# Tablero_Potencia_para_PDF.net
KiCad netlist of a schematic drawn in EAGLE
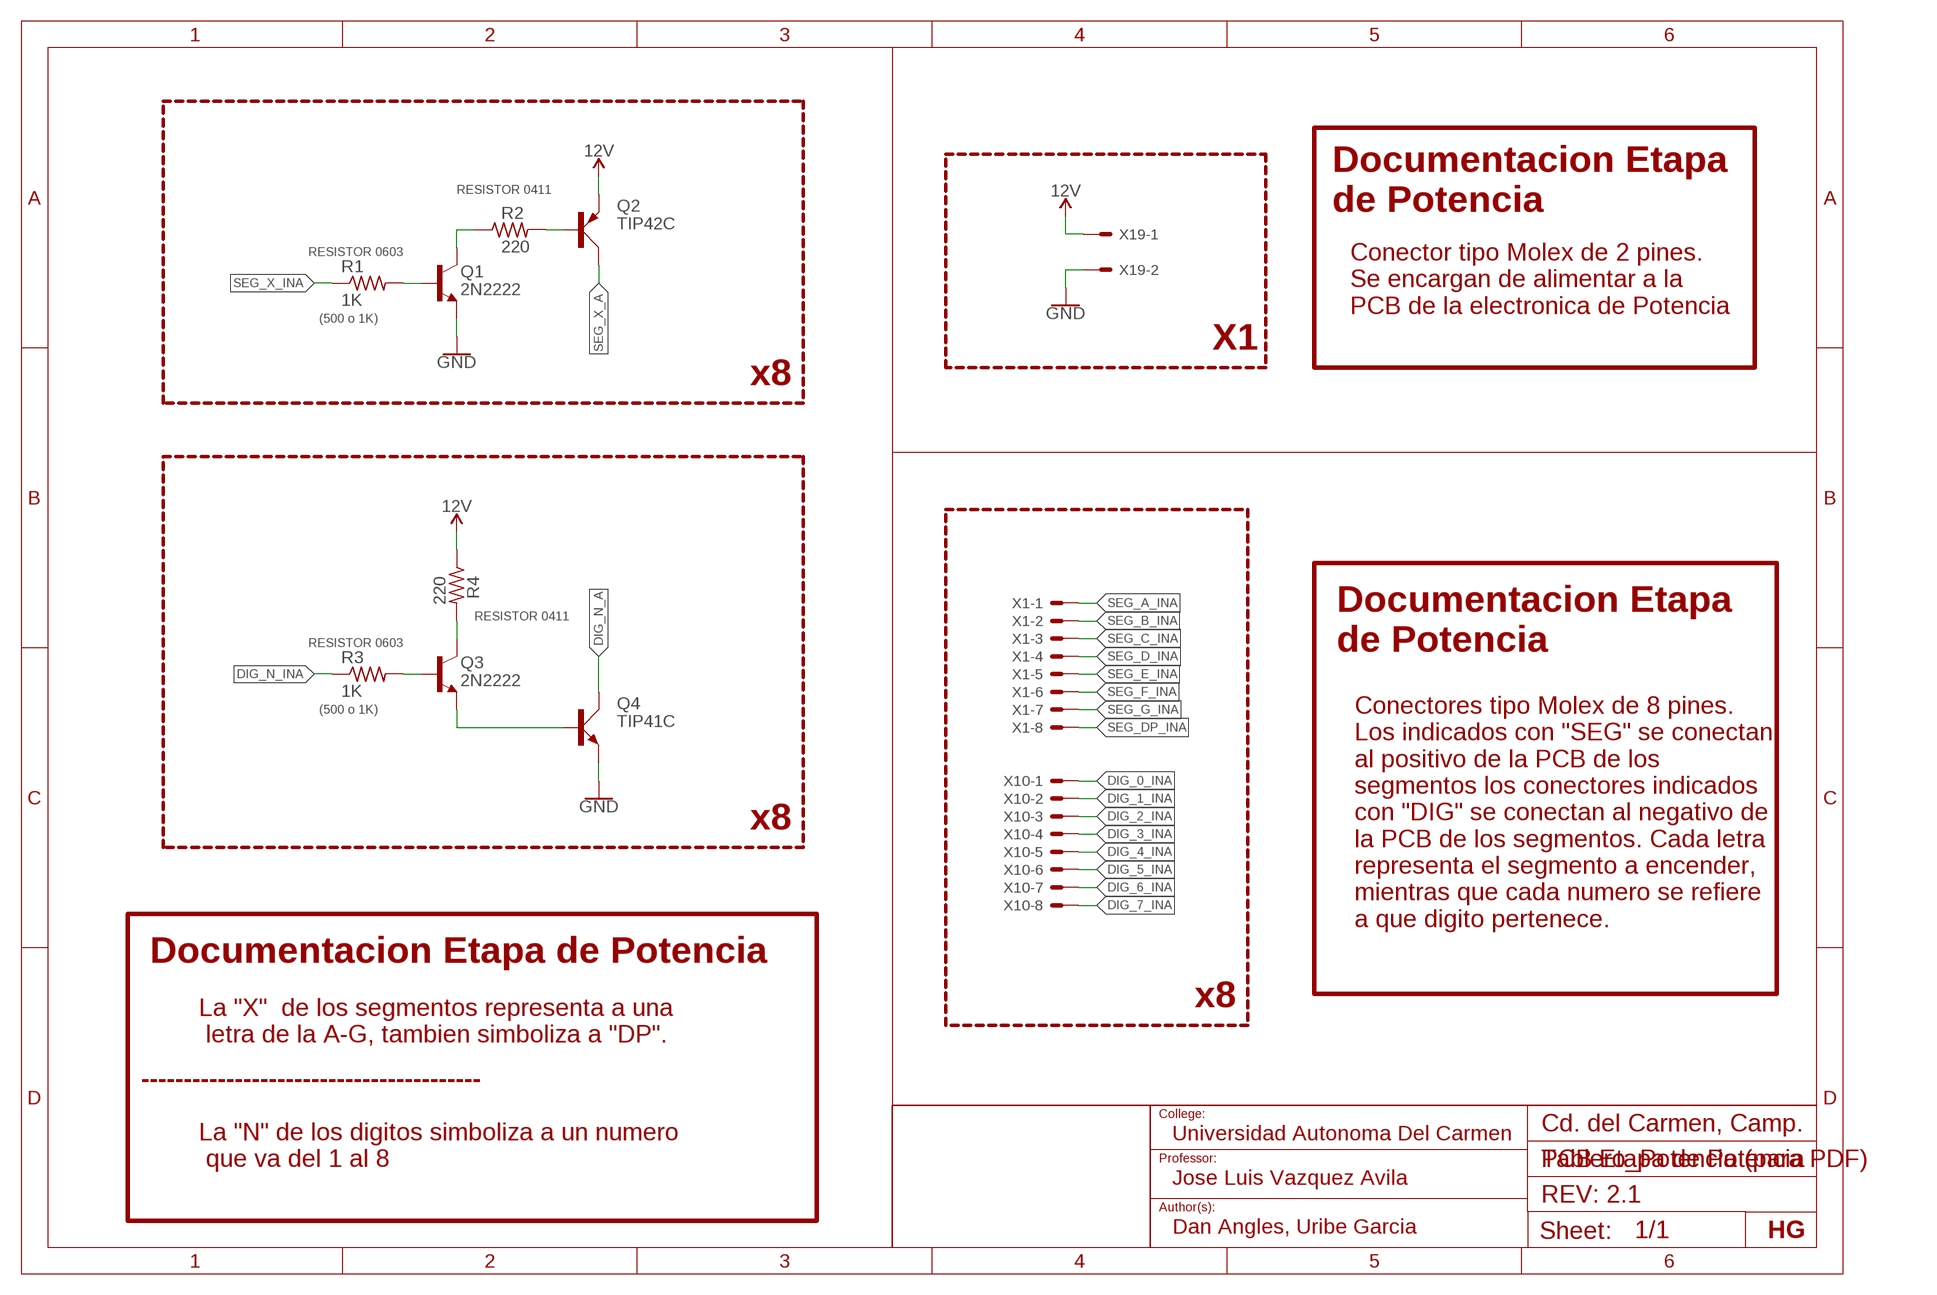
[diagram p0: schematic, sheet 1]

(export (version "E")
  (design (tool "Eeschema 10.0.6"))
  (components
    (comp (ref "Q1")
      (value "2N2222")
      (footprint "eagle-import:TO92")
      (libsource (lib "eagle-import") (part "BJT-NPNTO92"))
    )
    (comp (ref "Q2")
      (value "TIP42C")
      (footprint "eagle-import:TO220AV")
      (libsource (lib "eagle-import") (part "TIP42C"))
    )
    (comp (ref "Q3")
      (value "2N2222")
      (footprint "eagle-import:TO92")
      (libsource (lib "eagle-import") (part "BJT-NPNTO92"))
    )
    (comp (ref "Q4")
      (value "TIP41C")
      (footprint "eagle-import:TO220AV")
      (libsource (lib "eagle-import") (part "TIP41C"))
    )
    (comp (ref "R1")
      (value "1K")
      (footprint "eagle-import:R0603")
      (libsource (lib "eagle-import") (part "R-US_R0603"))
    )
    (comp (ref "R2")
      (value "220")
      (footprint "eagle-import:0411_15")
      (libsource (lib "eagle-import") (part "R-US_0411/15"))
    )
    (comp (ref "R3")
      (value "1K")
      (footprint "eagle-import:R0603")
      (libsource (lib "eagle-import") (part "R-US_R0603"))
    )
    (comp (ref "R4")
      (value "220")
      (footprint "eagle-import:0411_15")
      (libsource (lib "eagle-import") (part "R-US_0411/15"))
    )
    (comp (ref "X1")
      (value "KK-156-8")
      (footprint "eagle-import:KK-156-8")
      (fields (field (name "MF") "MOLEX"))
      (libsource (lib "eagle-import") (part "KK-156-8"))
    )
    (comp (ref "X10")
      (value "KK-156-8")
      (footprint "eagle-import:KK-156-8")
      (fields (field (name "MF") "MOLEX"))
      (libsource (lib "eagle-import") (part "KK-156-8"))
    )
    (comp (ref "X19")
      (value "KK-156-2")
      (footprint "eagle-import:KK-156-2")
      (fields (field (name "MF") "MOLEX"))
      (libsource (lib "eagle-import") (part "KK-156-2"))
    )
  )
  (nets
    (net (code "1") (name "12V") (class "Default")
      (node (ref "Q2") (pin "E") (pinfunction "E_E") (pintype "passive"))
      (node (ref "R4") (pin "1") (pinfunction "1_1") (pintype "passive"))
      (node (ref "X19") (pin "1") (pinfunction "S_1") (pintype "passive"))
    )
    (net (code "2") (name "DIG_0_INA") (class "Default")
      (node (ref "X10") (pin "1") (pinfunction "S_1") (pintype "passive"))
    )
    (net (code "3") (name "DIG_1_INA") (class "Default")
      (node (ref "X10") (pin "2") (pinfunction "S_2") (pintype "passive"))
    )
    (net (code "4") (name "DIG_2_INA") (class "Default")
      (node (ref "X10") (pin "3") (pinfunction "S_3") (pintype "passive"))
    )
    (net (code "5") (name "DIG_3_INA") (class "Default")
      (node (ref "X10") (pin "4") (pinfunction "S_4") (pintype "passive"))
    )
    (net (code "6") (name "DIG_4_INA") (class "Default")
      (node (ref "X10") (pin "5") (pinfunction "S_5") (pintype "passive"))
    )
    (net (code "7") (name "DIG_5_INA") (class "Default")
      (node (ref "X10") (pin "6") (pinfunction "S_6") (pintype "passive"))
    )
    (net (code "8") (name "DIG_6_INA") (class "Default")
      (node (ref "X10") (pin "7") (pinfunction "S_7") (pintype "passive"))
    )
    (net (code "9") (name "DIG_7_INA") (class "Default")
      (node (ref "X10") (pin "8") (pinfunction "S_8") (pintype "passive"))
    )
    (net (code "10") (name "DIG_N_A") (class "Default")
      (node (ref "Q4") (pin "C") (pinfunction "C_C") (pintype "passive"))
    )
    (net (code "11") (name "DIG_N_INA") (class "Default")
      (node (ref "R3") (pin "1") (pinfunction "1_1") (pintype "passive"))
    )
    (net (code "12") (name "GND") (class "Default")
      (node (ref "Q1") (pin "3") (pinfunction "E_3") (pintype "passive"))
      (node (ref "Q4") (pin "E") (pinfunction "E_E") (pintype "passive"))
      (node (ref "X19") (pin "2") (pinfunction "S_2") (pintype "passive"))
    )
    (net (code "13") (name "Net-(Q1-B)") (class "Default")
      (node (ref "Q1") (pin "2") (pinfunction "B_2") (pintype "passive"))
      (node (ref "R1") (pin "2") (pinfunction "2_2") (pintype "passive"))
    )
    (net (code "14") (name "Net-(Q1-C)") (class "Default")
      (node (ref "Q1") (pin "1") (pinfunction "C_1") (pintype "passive"))
      (node (ref "R2") (pin "1") (pinfunction "1_1") (pintype "passive"))
    )
    (net (code "15") (name "Net-(Q2-PadB)") (class "Default")
      (node (ref "Q2") (pin "B") (pinfunction "B_B") (pintype "passive"))
      (node (ref "R2") (pin "2") (pinfunction "2_2") (pintype "passive"))
    )
    (net (code "16") (name "Net-(Q3-B)") (class "Default")
      (node (ref "Q3") (pin "2") (pinfunction "B_2") (pintype "passive"))
      (node (ref "R3") (pin "2") (pinfunction "2_2") (pintype "passive"))
    )
    (net (code "17") (name "Net-(Q3-C)") (class "Default")
      (node (ref "Q3") (pin "1") (pinfunction "C_1") (pintype "passive"))
      (node (ref "R4") (pin "2") (pinfunction "2_2") (pintype "passive"))
    )
    (net (code "18") (name "Net-(Q3-E)") (class "Default")
      (node (ref "Q3") (pin "3") (pinfunction "E_3") (pintype "passive"))
      (node (ref "Q4") (pin "B") (pinfunction "B_B") (pintype "passive"))
    )
    (net (code "19") (name "SEG_A_INA") (class "Default")
      (node (ref "X1") (pin "1") (pinfunction "S_1") (pintype "passive"))
    )
    (net (code "20") (name "SEG_B_INA") (class "Default")
      (node (ref "X1") (pin "2") (pinfunction "S_2") (pintype "passive"))
    )
    (net (code "21") (name "SEG_C_INA") (class "Default")
      (node (ref "X1") (pin "3") (pinfunction "S_3") (pintype "passive"))
    )
    (net (code "22") (name "SEG_DP_INA") (class "Default")
      (node (ref "X1") (pin "8") (pinfunction "S_8") (pintype "passive"))
    )
    (net (code "23") (name "SEG_D_INA") (class "Default")
      (node (ref "X1") (pin "4") (pinfunction "S_4") (pintype "passive"))
    )
    (net (code "24") (name "SEG_E_INA") (class "Default")
      (node (ref "X1") (pin "5") (pinfunction "S_5") (pintype "passive"))
    )
    (net (code "25") (name "SEG_F_INA") (class "Default")
      (node (ref "X1") (pin "6") (pinfunction "S_6") (pintype "passive"))
    )
    (net (code "26") (name "SEG_G_INA") (class "Default")
      (node (ref "X1") (pin "7") (pinfunction "S_7") (pintype "passive"))
    )
    (net (code "27") (name "SEG_X_A") (class "Default")
      (node (ref "Q2") (pin "C") (pinfunction "C_C") (pintype "passive"))
    )
    (net (code "28") (name "SEG_X_INA") (class "Default")
      (node (ref "R1") (pin "1") (pinfunction "1_1") (pintype "passive"))
    )
  )
)
